# system-schematic.net
KiCad netlist of a schematic drawn in Altium Designer
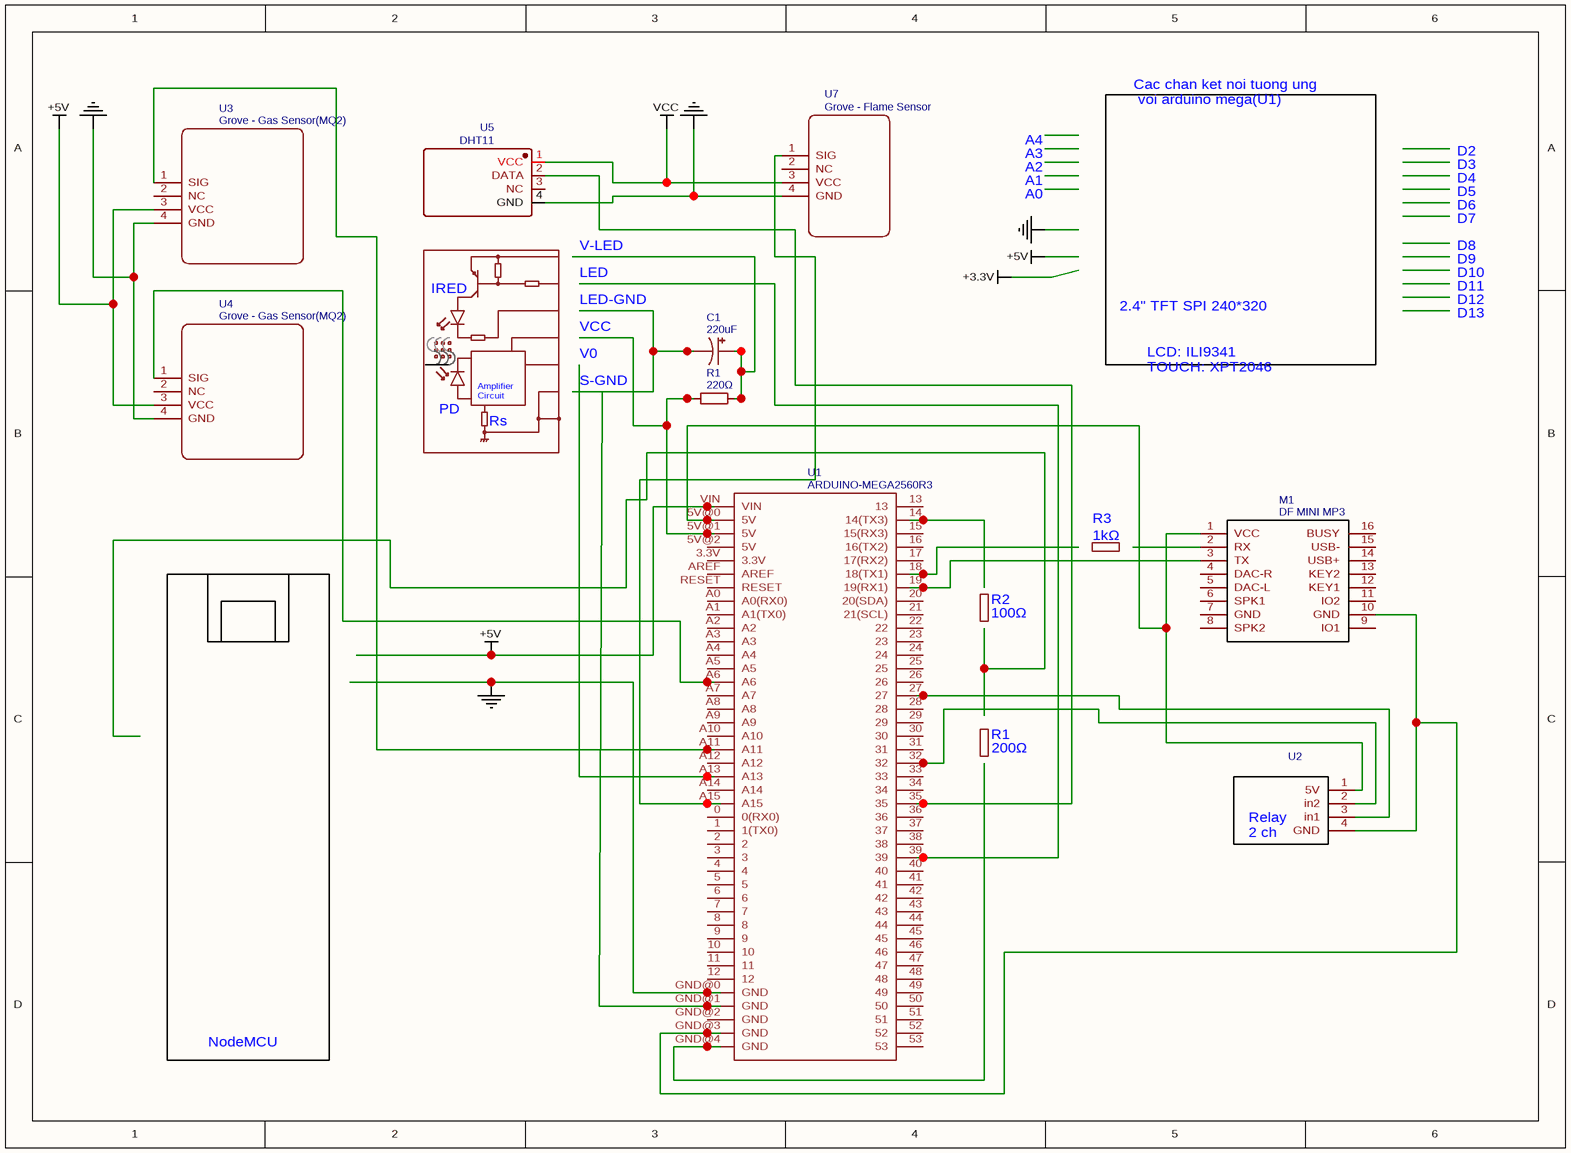
[diagram p0: system-schematic.schdoc]

(export (version "E")
  (design (tool "Eeschema 10.0.6"))
  (components
    (comp (ref "C1")
      (value "220uF")
      (fields (field (name "BOM_MANUFACTURER PART") "?"))
      (libsource (lib "altium-import") (part "root_3_220uF_"))
    )
    (comp (ref "M1")
      (value "DF MINI MP3")
      (fields (field (name "BOM_MANUFACTURER PART") "New SchematicLib") (field (name "CONTRIBUTOR") "grichm"))
      (libsource (lib "altium-import") (part "root_0_DF MINI MP3_"))
    )
    (comp (ref "R1")
      (value "220Ω")
      (fields (field (name "BOM_MANUFACTURER PART") "?"))
      (libsource (lib "altium-import") (part "root_0_220Ω_"))
    )
    (comp (ref "U1")
      (value "ARDUINO-MEGA2560R3")
      (description "Arduino Mega board footprint")
      (fields (field (name "BOM_MANUFACTURER PART") "?") (field (name "CONTRIBUTOR") "SparkFun"))
      (libsource (lib "altium-import") (part "root_0_ARDUINO-MEGA2560R3_"))
    )
    (comp (ref "U2")
      (value "NO")
      (fields (field (name "BOM_MANUFACTURER PART") "?") (field (name "CONTRIBUTOR") "rowid"))
      (libsource (lib "altium-import") (part "root_0_NO_"))
    )
    (comp (ref "U3")
      (value "Grove - Gas Sensor(MQ2)")
      (fields (field (name "BOM_SUPPLIER PART") "undefined") (field (name "BOM_MANUFACTURER PART") "?"))
      (libsource (lib "altium-import") (part "root_0_Grove - Gas Sensor(MQ2)_"))
    )
    (comp (ref "U4")
      (value "Grove - Gas Sensor(MQ2)")
      (fields (field (name "BOM_SUPPLIER PART") "undefined") (field (name "BOM_MANUFACTURER PART") "?"))
      (libsource (lib "altium-import") (part "root_0_Grove - Gas Sensor(MQ2)_"))
    )
    (comp (ref "U5")
      (value "DHT11")
      (fields (field (name "BOM_SUPPLIER PART") "C117051") (field (name "CONTRIBUTOR") "LCSC"))
      (libsource (lib "altium-import") (part "root_0_DHT11_"))
    )
    (comp (ref "U7")
      (value "Grove - Flame Sensor")
      (fields (field (name "BOM_SUPPLIER PART") "undefined") (field (name "BOM_MANUFACTURER PART") "?"))
      (libsource (lib "altium-import") (part "root_0_Grove - Flame Sensor_"))
    )
  )
  (nets
    (net (code "2") (name "+5V") (class "Default")
      (node (ref "U1") (pin "VIN") (pinfunction "VIN_VIN") (pintype "passive"))
      (node (ref "U3") (pin "3") (pinfunction "VCC_3") (pintype "passive"))
      (node (ref "U4") (pin "3") (pinfunction "VCC_3") (pintype "passive"))
    )
    (net (code "3") (name "GND") (class "Default")
      (node (ref "U1") (pin "GND@0") (pinfunction "GND_GND@0") (pintype "passive"))
      (node (ref "U3") (pin "4") (pinfunction "GND_4") (pintype "passive"))
      (node (ref "U4") (pin "4") (pinfunction "GND_4") (pintype "passive"))
      (node (ref "U5") (pin "4") (pinfunction "GND_4") (pintype "passive"))
      (node (ref "U7") (pin "4") (pinfunction "GND_4") (pintype "passive"))
    )
    (net (code "4") (name "Net-(C1-Pad2)") (class "Default")
      (node (ref "C1") (pin "2") (pinfunction "2_2") (pintype "passive"))
      (node (ref "U1") (pin "GND@1") (pinfunction "GND_GND@1") (pintype "passive"))
    )
    (net (code "5") (name "Net-(M1-TX)") (class "Default")
      (node (ref "M1") (pin "3") (pinfunction "TX_3") (pintype "passive"))
      (node (ref "U1") (pin "19") (pinfunction "19(RX1)_19") (pintype "passive"))
    )
    (net (code "6") (name "Net-(M1-VCC)") (class "Default")
      (node (ref "M1") (pin "1") (pinfunction "VCC_1") (pintype "passive"))
      (node (ref "U1") (pin "5V@0") (pinfunction "5V_5V@0") (pintype "passive"))
      (node (ref "U2") (pin "1") (pinfunction "5V_1") (pintype "passive"))
    )
    (net (code "7") (name "Net-(U2-GND)") (class "Default")
      (node (ref "M1") (pin "10") (pinfunction "GND_10") (pintype "passive"))
      (node (ref "U1") (pin "GND@3") (pinfunction "GND_GND@3") (pintype "passive"))
      (node (ref "U2") (pin "4") (pinfunction "GND_4") (pintype "passive"))
    )
    (net (code "8") (name "Net-(U2-in1)") (class "Default")
      (node (ref "U1") (pin "27") (pinfunction "27_27") (pintype "passive"))
      (node (ref "U2") (pin "3") (pinfunction "in1_3") (pintype "passive"))
    )
    (net (code "9") (name "Net-(U2-in2)") (class "Default")
      (node (ref "U1") (pin "32") (pinfunction "32_32") (pintype "passive"))
      (node (ref "U2") (pin "2") (pinfunction "in2_2") (pintype "passive"))
    )
    (net (code "10") (name "Net-(U3-SIG)") (class "Default")
      (node (ref "U1") (pin "A11") (pinfunction "A11_A11") (pintype "passive"))
      (node (ref "U3") (pin "1") (pinfunction "SIG_1") (pintype "passive"))
    )
    (net (code "11") (name "Net-(U4-SIG)") (class "Default")
      (node (ref "U1") (pin "A6") (pinfunction "A6_A6") (pintype "passive"))
      (node (ref "U4") (pin "1") (pinfunction "SIG_1") (pintype "passive"))
    )
    (net (code "12") (name "Net-(U5-DATA)") (class "Default")
      (node (ref "U1") (pin "35") (pinfunction "35_35") (pintype "passive"))
      (node (ref "U5") (pin "2") (pinfunction "DATA_2") (pintype "passive"))
    )
    (net (code "13") (name "Net-(U7-SIG)") (class "Default")
      (node (ref "U1") (pin "A15") (pinfunction "A15_A15") (pintype "passive"))
      (node (ref "U7") (pin "1") (pinfunction "SIG_1") (pintype "passive"))
    )
    (net (code "14") (name "VCC") (class "Default")
      (node (ref "U5") (pin "1") (pinfunction "VCC_1") (pintype "passive"))
      (node (ref "U7") (pin "3") (pinfunction "VCC_3") (pintype "passive"))
    )
    (net (code "15") (name "unconnected-(C1-Pad1)") (class "Default")
      (node (ref "C1") (pin "1") (pinfunction "1_1") (pintype "passive"))
    )
    (net (code "16") (name "unconnected-(M1-BUSY-Pad16)") (class "Default")
      (node (ref "M1") (pin "16") (pinfunction "BUSY_16") (pintype "passive"))
    )
    (net (code "17") (name "unconnected-(M1-DAC-L-Pad5)") (class "Default")
      (node (ref "M1") (pin "5") (pinfunction "DAC-L_5") (pintype "passive"))
    )
    (net (code "18") (name "unconnected-(M1-DAC-R-Pad4)") (class "Default")
      (node (ref "M1") (pin "4") (pinfunction "DAC-R_4") (pintype "passive"))
    )
    (net (code "19") (name "unconnected-(M1-GND-Pad7)") (class "Default")
      (node (ref "M1") (pin "7") (pinfunction "GND_7") (pintype "passive"))
    )
    (net (code "20") (name "unconnected-(M1-IO1-Pad9)") (class "Default")
      (node (ref "M1") (pin "9") (pinfunction "IO1_9") (pintype "passive"))
    )
    (net (code "21") (name "unconnected-(M1-IO2-Pad11)") (class "Default")
      (node (ref "M1") (pin "11") (pinfunction "IO2_11") (pintype "passive"))
    )
    (net (code "22") (name "unconnected-(M1-KEY1-Pad12)") (class "Default")
      (node (ref "M1") (pin "12") (pinfunction "KEY1_12") (pintype "passive"))
    )
    (net (code "23") (name "unconnected-(M1-KEY2-Pad13)") (class "Default")
      (node (ref "M1") (pin "13") (pinfunction "KEY2_13") (pintype "passive"))
    )
    (net (code "24") (name "unconnected-(M1-RX-Pad2)") (class "Default")
      (node (ref "M1") (pin "2") (pinfunction "RX_2") (pintype "passive"))
    )
    (net (code "25") (name "unconnected-(M1-SPK1-Pad6)") (class "Default")
      (node (ref "M1") (pin "6") (pinfunction "SPK1_6") (pintype "passive"))
    )
    (net (code "26") (name "unconnected-(M1-SPK2-Pad8)") (class "Default")
      (node (ref "M1") (pin "8") (pinfunction "SPK2_8") (pintype "passive"))
    )
    (net (code "27") (name "unconnected-(M1-USB+-Pad14)") (class "Default")
      (node (ref "M1") (pin "14") (pinfunction "USB+_14") (pintype "passive"))
    )
    (net (code "28") (name "unconnected-(M1-USB--Pad15)") (class "Default")
      (node (ref "M1") (pin "15") (pinfunction "USB-_15") (pintype "passive"))
    )
    (net (code "29") (name "unconnected-(R1-Pad1)") (class "Default")
      (node (ref "R1") (pin "1") (pinfunction "1_1") (pintype "passive"))
    )
    (net (code "30") (name "unconnected-(R1-Pad2)") (class "Default")
      (node (ref "R1") (pin "2") (pinfunction "2_2") (pintype "passive"))
    )
    (net (code "31") (name "unconnected-(U1-0(RX0)-Pad0)") (class "Default")
      (node (ref "U1") (pin "0") (pinfunction "0(RX0)_0") (pintype "passive"))
    )
    (net (code "32") (name "unconnected-(U1-1(TX0)-Pad1)") (class "Default")
      (node (ref "U1") (pin "1") (pinfunction "1(TX0)_1") (pintype "passive"))
    )
    (net (code "33") (name "unconnected-(U1-5V-Pad5V@1)") (class "Default")
      (node (ref "U1") (pin "5V@1") (pinfunction "5V_5V@1") (pintype "passive"))
    )
    (net (code "34") (name "unconnected-(U1-5V-Pad5V@2)") (class "Default")
      (node (ref "U1") (pin "5V@2") (pinfunction "5V_5V@2") (pintype "passive"))
    )
    (net (code "35") (name "unconnected-(U1-14(TX3)-Pad14)") (class "Default")
      (node (ref "U1") (pin "14") (pinfunction "14(TX3)_14") (pintype "passive"))
    )
    (net (code "36") (name "unconnected-(U1-15(RX3)-Pad15)") (class "Default")
      (node (ref "U1") (pin "15") (pinfunction "15(RX3)_15") (pintype "passive"))
    )
    (net (code "37") (name "unconnected-(U1-16(TX2)-Pad16)") (class "Default")
      (node (ref "U1") (pin "16") (pinfunction "16(TX2)_16") (pintype "passive"))
    )
    (net (code "38") (name "unconnected-(U1-17(RX2)-Pad17)") (class "Default")
      (node (ref "U1") (pin "17") (pinfunction "17(RX2)_17") (pintype "passive"))
    )
    (net (code "39") (name "unconnected-(U1-18(TX1)-Pad18)") (class "Default")
      (node (ref "U1") (pin "18") (pinfunction "18(TX1)_18") (pintype "passive"))
    )
    (net (code "40") (name "unconnected-(U1-20(SDA)-Pad20)") (class "Default")
      (node (ref "U1") (pin "20") (pinfunction "20(SDA)_20") (pintype "passive"))
    )
    (net (code "41") (name "unconnected-(U1-21(SCL)-Pad21)") (class "Default")
      (node (ref "U1") (pin "21") (pinfunction "21(SCL)_21") (pintype "passive"))
    )
    (net (code "42") (name "unconnected-(U1-A0(RX0)-PadA0)") (class "Default")
      (node (ref "U1") (pin "A0") (pinfunction "A0(RX0)_A0") (pintype "passive"))
    )
    (net (code "43") (name "unconnected-(U1-A1(TX0)-PadA1)") (class "Default")
      (node (ref "U1") (pin "A1") (pinfunction "A1(TX0)_A1") (pintype "passive"))
    )
    (net (code "44") (name "unconnected-(U1-GND-PadGND@2)") (class "Default")
      (node (ref "U1") (pin "GND@2") (pinfunction "GND_GND@2") (pintype "passive"))
    )
    (net (code "45") (name "unconnected-(U1-GND-PadGND@4)") (class "Default")
      (node (ref "U1") (pin "GND@4") (pinfunction "GND_GND@4") (pintype "passive"))
    )
    (net (code "46") (name "unconnected-(U1-Pad2)") (class "Default")
      (node (ref "U1") (pin "2") (pinfunction "2_2") (pintype "passive"))
    )
    (net (code "47") (name "unconnected-(U1-Pad3)") (class "Default")
      (node (ref "U1") (pin "3") (pinfunction "3_3") (pintype "passive"))
    )
    (net (code "48") (name "unconnected-(U1-Pad3.3V)") (class "Default")
      (node (ref "U1") (pin "3.3V") (pinfunction "3.3V_3.3V") (pintype "passive"))
    )
    (net (code "49") (name "unconnected-(U1-Pad4)") (class "Default")
      (node (ref "U1") (pin "4") (pinfunction "4_4") (pintype "passive"))
    )
    (net (code "50") (name "unconnected-(U1-Pad5)") (class "Default")
      (node (ref "U1") (pin "5") (pinfunction "5_5") (pintype "passive"))
    )
    (net (code "51") (name "unconnected-(U1-Pad6)") (class "Default")
      (node (ref "U1") (pin "6") (pinfunction "6_6") (pintype "passive"))
    )
    (net (code "52") (name "unconnected-(U1-Pad7)") (class "Default")
      (node (ref "U1") (pin "7") (pinfunction "7_7") (pintype "passive"))
    )
    (net (code "53") (name "unconnected-(U1-Pad8)") (class "Default")
      (node (ref "U1") (pin "8") (pinfunction "8_8") (pintype "passive"))
    )
    (net (code "54") (name "unconnected-(U1-Pad9)") (class "Default")
      (node (ref "U1") (pin "9") (pinfunction "9_9") (pintype "passive"))
    )
    (net (code "55") (name "unconnected-(U1-Pad10)") (class "Default")
      (node (ref "U1") (pin "10") (pinfunction "10_10") (pintype "passive"))
    )
    (net (code "56") (name "unconnected-(U1-Pad11)") (class "Default")
      (node (ref "U1") (pin "11") (pinfunction "11_11") (pintype "passive"))
    )
    (net (code "57") (name "unconnected-(U1-Pad12)") (class "Default")
      (node (ref "U1") (pin "12") (pinfunction "12_12") (pintype "passive"))
    )
    (net (code "58") (name "unconnected-(U1-Pad13)") (class "Default")
      (node (ref "U1") (pin "13") (pinfunction "13_13") (pintype "passive"))
    )
    (net (code "59") (name "unconnected-(U1-Pad22)") (class "Default")
      (node (ref "U1") (pin "22") (pinfunction "22_22") (pintype "passive"))
    )
    (net (code "60") (name "unconnected-(U1-Pad23)") (class "Default")
      (node (ref "U1") (pin "23") (pinfunction "23_23") (pintype "passive"))
    )
    (net (code "61") (name "unconnected-(U1-Pad24)") (class "Default")
      (node (ref "U1") (pin "24") (pinfunction "24_24") (pintype "passive"))
    )
    (net (code "62") (name "unconnected-(U1-Pad25)") (class "Default")
      (node (ref "U1") (pin "25") (pinfunction "25_25") (pintype "passive"))
    )
    (net (code "63") (name "unconnected-(U1-Pad26)") (class "Default")
      (node (ref "U1") (pin "26") (pinfunction "26_26") (pintype "passive"))
    )
    (net (code "64") (name "unconnected-(U1-Pad28)") (class "Default")
      (node (ref "U1") (pin "28") (pinfunction "28_28") (pintype "passive"))
    )
    (net (code "65") (name "unconnected-(U1-Pad29)") (class "Default")
      (node (ref "U1") (pin "29") (pinfunction "29_29") (pintype "passive"))
    )
    (net (code "66") (name "unconnected-(U1-Pad30)") (class "Default")
      (node (ref "U1") (pin "30") (pinfunction "30_30") (pintype "passive"))
    )
    (net (code "67") (name "unconnected-(U1-Pad31)") (class "Default")
      (node (ref "U1") (pin "31") (pinfunction "31_31") (pintype "passive"))
    )
    (net (code "68") (name "unconnected-(U1-Pad33)") (class "Default")
      (node (ref "U1") (pin "33") (pinfunction "33_33") (pintype "passive"))
    )
    (net (code "69") (name "unconnected-(U1-Pad34)") (class "Default")
      (node (ref "U1") (pin "34") (pinfunction "34_34") (pintype "passive"))
    )
    (net (code "70") (name "unconnected-(U1-Pad36)") (class "Default")
      (node (ref "U1") (pin "36") (pinfunction "36_36") (pintype "passive"))
    )
    (net (code "71") (name "unconnected-(U1-Pad37)") (class "Default")
      (node (ref "U1") (pin "37") (pinfunction "37_37") (pintype "passive"))
    )
    (net (code "72") (name "unconnected-(U1-Pad38)") (class "Default")
      (node (ref "U1") (pin "38") (pinfunction "38_38") (pintype "passive"))
    )
    (net (code "73") (name "unconnected-(U1-Pad39)") (class "Default")
      (node (ref "U1") (pin "39") (pinfunction "39_39") (pintype "passive"))
    )
    (net (code "74") (name "unconnected-(U1-Pad40)") (class "Default")
      (node (ref "U1") (pin "40") (pinfunction "40_40") (pintype "passive"))
    )
    (net (code "75") (name "unconnected-(U1-Pad41)") (class "Default")
      (node (ref "U1") (pin "41") (pinfunction "41_41") (pintype "passive"))
    )
    (net (code "76") (name "unconnected-(U1-Pad42)") (class "Default")
      (node (ref "U1") (pin "42") (pinfunction "42_42") (pintype "passive"))
    )
    (net (code "77") (name "unconnected-(U1-Pad43)") (class "Default")
      (node (ref "U1") (pin "43") (pinfunction "43_43") (pintype "passive"))
    )
    (net (code "78") (name "unconnected-(U1-Pad44)") (class "Default")
      (node (ref "U1") (pin "44") (pinfunction "44_44") (pintype "passive"))
    )
    (net (code "79") (name "unconnected-(U1-Pad45)") (class "Default")
      (node (ref "U1") (pin "45") (pinfunction "45_45") (pintype "passive"))
    )
    (net (code "80") (name "unconnected-(U1-Pad46)") (class "Default")
      (node (ref "U1") (pin "46") (pinfunction "46_46") (pintype "passive"))
    )
    (net (code "81") (name "unconnected-(U1-Pad47)") (class "Default")
      (node (ref "U1") (pin "47") (pinfunction "47_47") (pintype "passive"))
    )
    (net (code "82") (name "unconnected-(U1-Pad48)") (class "Default")
      (node (ref "U1") (pin "48") (pinfunction "48_48") (pintype "passive"))
    )
    (net (code "83") (name "unconnected-(U1-Pad49)") (class "Default")
      (node (ref "U1") (pin "49") (pinfunction "49_49") (pintype "passive"))
    )
    (net (code "84") (name "unconnected-(U1-Pad50)") (class "Default")
      (node (ref "U1") (pin "50") (pinfunction "50_50") (pintype "passive"))
    )
    (net (code "85") (name "unconnected-(U1-Pad51)") (class "Default")
      (node (ref "U1") (pin "51") (pinfunction "51_51") (pintype "passive"))
    )
    (net (code "86") (name "unconnected-(U1-Pad52)") (class "Default")
      (node (ref "U1") (pin "52") (pinfunction "52_52") (pintype "passive"))
    )
    (net (code "87") (name "unconnected-(U1-Pad53)") (class "Default")
      (node (ref "U1") (pin "53") (pinfunction "53_53") (pintype "passive"))
    )
    (net (code "88") (name "unconnected-(U1-PadA2)") (class "Default")
      (node (ref "U1") (pin "A2") (pinfunction "A2_A2") (pintype "passive"))
    )
    (net (code "89") (name "unconnected-(U1-PadA3)") (class "Default")
      (node (ref "U1") (pin "A3") (pinfunction "A3_A3") (pintype "passive"))
    )
    (net (code "90") (name "unconnected-(U1-PadA4)") (class "Default")
      (node (ref "U1") (pin "A4") (pinfunction "A4_A4") (pintype "passive"))
    )
    (net (code "91") (name "unconnected-(U1-PadA5)") (class "Default")
      (node (ref "U1") (pin "A5") (pinfunction "A5_A5") (pintype "passive"))
    )
    (net (code "92") (name "unconnected-(U1-PadA7)") (class "Default")
      (node (ref "U1") (pin "A7") (pinfunction "A7_A7") (pintype "passive"))
    )
    (net (code "93") (name "unconnected-(U1-PadA8)") (class "Default")
      (node (ref "U1") (pin "A8") (pinfunction "A8_A8") (pintype "passive"))
    )
    (net (code "94") (name "unconnected-(U1-PadA9)") (class "Default")
      (node (ref "U1") (pin "A9") (pinfunction "A9_A9") (pintype "passive"))
    )
    (net (code "95") (name "unconnected-(U1-PadA10)") (class "Default")
      (node (ref "U1") (pin "A10") (pinfunction "A10_A10") (pintype "passive"))
    )
    (net (code "96") (name "unconnected-(U1-PadA12)") (class "Default")
      (node (ref "U1") (pin "A12") (pinfunction "A12_A12") (pintype "passive"))
    )
    (net (code "97") (name "unconnected-(U1-PadA13)") (class "Default")
      (node (ref "U1") (pin "A13") (pinfunction "A13_A13") (pintype "passive"))
    )
    (net (code "98") (name "unconnected-(U1-PadA14)") (class "Default")
      (node (ref "U1") (pin "A14") (pinfunction "A14_A14") (pintype "passive"))
    )
    (net (code "99") (name "unconnected-(U1-PadAREF)") (class "Default")
      (node (ref "U1") (pin "AREF") (pinfunction "AREF_AREF") (pintype "passive"))
    )
    (net (code "100") (name "unconnected-(U1-PadRESET)") (class "Default")
      (node (ref "U1") (pin "RESET") (pinfunction "RESET_RESET") (pintype "passive"))
    )
    (net (code "101") (name "unconnected-(U3-NC-Pad2)") (class "Default")
      (node (ref "U3") (pin "2") (pinfunction "NC_2") (pintype "passive"))
    )
    (net (code "102") (name "unconnected-(U4-NC-Pad2)") (class "Default")
      (node (ref "U4") (pin "2") (pinfunction "NC_2") (pintype "passive"))
    )
    (net (code "103") (name "unconnected-(U5-NC-Pad3)") (class "Default")
      (node (ref "U5") (pin "3") (pinfunction "NC_3") (pintype "passive"))
    )
    (net (code "104") (name "unconnected-(U7-NC-Pad2)") (class "Default")
      (node (ref "U7") (pin "2") (pinfunction "NC_2") (pintype "passive"))
    )
  )
)
